# R450E.net
KiCad netlist of a schematic drawn in EAGLE
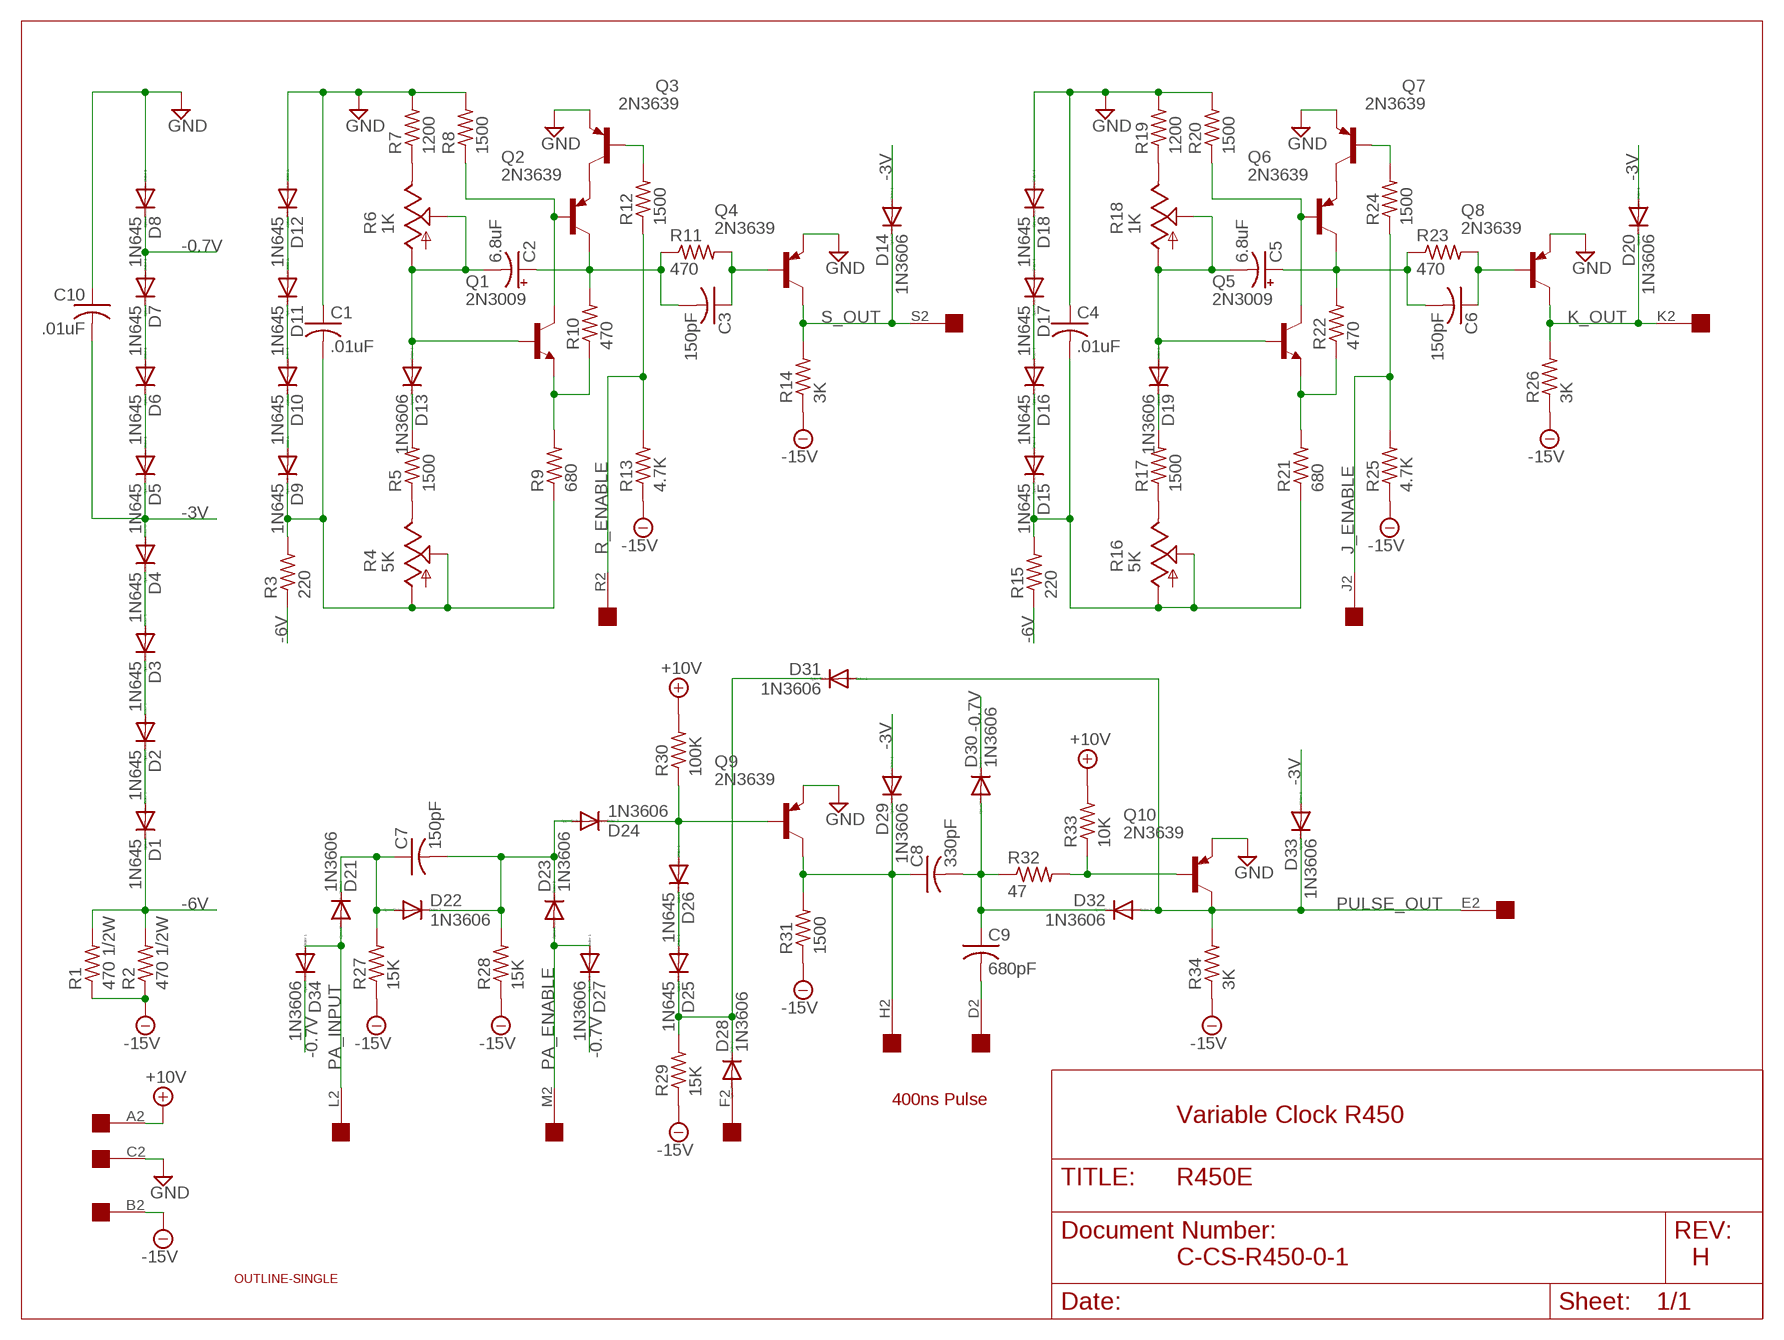
[diagram p0: schematic, sheet 1]

(export (version "E")
  (design (tool "Eeschema 10.0.6"))
  (components
    (comp (ref "C1")
      (value ".01uF")
      (footprint "eagle-import:C050-025X075")
      (libsource (lib "eagle-import") (part "C-US050-025X075"))
    )
    (comp (ref "C2")
      (value "6.8uF")
      (footprint "eagle-import:E12-4")
      (libsource (lib "eagle-import") (part "CPOL-USE12-4AXIAL"))
    )
    (comp (ref "C3")
      (value "150pF")
      (footprint "eagle-import:C075-032X103")
      (libsource (lib "eagle-import") (part "C-US075-032X103"))
    )
    (comp (ref "C4")
      (value ".01uF")
      (footprint "eagle-import:C050-025X075")
      (libsource (lib "eagle-import") (part "C-US050-025X075"))
    )
    (comp (ref "C5")
      (value "6.8uF")
      (footprint "eagle-import:E12-4")
      (libsource (lib "eagle-import") (part "CPOL-USE12-4AXIAL"))
    )
    (comp (ref "C6")
      (value "150pF")
      (footprint "eagle-import:C075-032X103")
      (libsource (lib "eagle-import") (part "C-US075-032X103"))
    )
    (comp (ref "C7")
      (value "150pF")
      (footprint "eagle-import:C075-032X103")
      (libsource (lib "eagle-import") (part "C-US075-032X103"))
    )
    (comp (ref "C8")
      (value "330pF")
      (footprint "eagle-import:C075-032X103")
      (libsource (lib "eagle-import") (part "C-US075-032X103"))
    )
    (comp (ref "C9")
      (value "680pF")
      (footprint "eagle-import:C075-032X103")
      (libsource (lib "eagle-import") (part "C-US075-032X103"))
    )
    (comp (ref "C10")
      (value ".01uF")
      (footprint "eagle-import:C050-025X075")
      (libsource (lib "eagle-import") (part "C-US050-025X075"))
    )
    (comp (ref "D1")
      (value "1N645")
      (footprint "eagle-import:DO35-10")
      (libsource (lib "eagle-import") (part "1N4148DO35-10"))
    )
    (comp (ref "D2")
      (value "1N645")
      (footprint "eagle-import:DO35-10")
      (libsource (lib "eagle-import") (part "1N4148DO35-10"))
    )
    (comp (ref "D3")
      (value "1N645")
      (footprint "eagle-import:DO35-10")
      (libsource (lib "eagle-import") (part "1N4148DO35-10"))
    )
    (comp (ref "D4")
      (value "1N645")
      (footprint "eagle-import:DO35-10")
      (libsource (lib "eagle-import") (part "1N4148DO35-10"))
    )
    (comp (ref "D5")
      (value "1N645")
      (footprint "eagle-import:DO35-10")
      (libsource (lib "eagle-import") (part "1N4148DO35-10"))
    )
    (comp (ref "D6")
      (value "1N645")
      (footprint "eagle-import:DO35-10")
      (libsource (lib "eagle-import") (part "1N4148DO35-10"))
    )
    (comp (ref "D7")
      (value "1N645")
      (footprint "eagle-import:DO35-10")
      (libsource (lib "eagle-import") (part "1N4148DO35-10"))
    )
    (comp (ref "D8")
      (value "1N645")
      (footprint "eagle-import:DO35-10")
      (libsource (lib "eagle-import") (part "1N4148DO35-10"))
    )
    (comp (ref "D9")
      (value "1N645")
      (footprint "eagle-import:DO35-10")
      (libsource (lib "eagle-import") (part "1N4148DO35-10"))
    )
    (comp (ref "D10")
      (value "1N645")
      (footprint "eagle-import:DO35-10")
      (libsource (lib "eagle-import") (part "1N4148DO35-10"))
    )
    (comp (ref "D11")
      (value "1N645")
      (footprint "eagle-import:DO35-10")
      (libsource (lib "eagle-import") (part "1N4148DO35-10"))
    )
    (comp (ref "D12")
      (value "1N645")
      (footprint "eagle-import:DO35-10")
      (libsource (lib "eagle-import") (part "1N4148DO35-10"))
    )
    (comp (ref "D13")
      (value "1N3606")
      (footprint "eagle-import:DO35-10")
      (libsource (lib "eagle-import") (part "1N4148DO35-10"))
    )
    (comp (ref "D14")
      (value "1N3606")
      (footprint "eagle-import:DO35-10")
      (libsource (lib "eagle-import") (part "1N4148DO35-10"))
    )
    (comp (ref "D15")
      (value "1N645")
      (footprint "eagle-import:DO35-10")
      (libsource (lib "eagle-import") (part "1N4148DO35-10"))
    )
    (comp (ref "D16")
      (value "1N645")
      (footprint "eagle-import:DO35-10")
      (libsource (lib "eagle-import") (part "1N4148DO35-10"))
    )
    (comp (ref "D17")
      (value "1N645")
      (footprint "eagle-import:DO35-10")
      (libsource (lib "eagle-import") (part "1N4148DO35-10"))
    )
    (comp (ref "D18")
      (value "1N645")
      (footprint "eagle-import:DO35-10")
      (libsource (lib "eagle-import") (part "1N4148DO35-10"))
    )
    (comp (ref "D19")
      (value "1N3606")
      (footprint "eagle-import:DO35-10")
      (libsource (lib "eagle-import") (part "1N4148DO35-10"))
    )
    (comp (ref "D20")
      (value "1N3606")
      (footprint "eagle-import:DO35-10")
      (libsource (lib "eagle-import") (part "1N4148DO35-10"))
    )
    (comp (ref "D21")
      (value "1N3606")
      (footprint "eagle-import:DO35-10")
      (libsource (lib "eagle-import") (part "1N4148DO35-10"))
    )
    (comp (ref "D22")
      (value "1N3606")
      (footprint "eagle-import:DO35-10")
      (libsource (lib "eagle-import") (part "1N4148DO35-10"))
    )
    (comp (ref "D23")
      (value "1N3606")
      (footprint "eagle-import:DO35-10")
      (libsource (lib "eagle-import") (part "1N4148DO35-10"))
    )
    (comp (ref "D24")
      (value "1N3606")
      (footprint "eagle-import:DO35-10")
      (libsource (lib "eagle-import") (part "1N4148DO35-10"))
    )
    (comp (ref "D25")
      (value "1N645")
      (footprint "eagle-import:DO35-10")
      (libsource (lib "eagle-import") (part "1N4148DO35-10"))
    )
    (comp (ref "D26")
      (value "1N645")
      (footprint "eagle-import:DO35-10")
      (libsource (lib "eagle-import") (part "1N4148DO35-10"))
    )
    (comp (ref "D27")
      (value "1N3606")
      (footprint "eagle-import:DO35-10")
      (libsource (lib "eagle-import") (part "1N4148DO35-10"))
    )
    (comp (ref "D28")
      (value "1N3606")
      (footprint "eagle-import:DO35-10")
      (libsource (lib "eagle-import") (part "1N4148DO35-10"))
    )
    (comp (ref "D29")
      (value "1N3606")
      (footprint "eagle-import:DO35-10")
      (libsource (lib "eagle-import") (part "1N4148DO35-10"))
    )
    (comp (ref "D30")
      (value "1N3606")
      (footprint "eagle-import:DO35-10")
      (libsource (lib "eagle-import") (part "1N4148DO35-10"))
    )
    (comp (ref "D31")
      (value "1N3606")
      (footprint "eagle-import:DO35-10")
      (libsource (lib "eagle-import") (part "1N4148DO35-10"))
    )
    (comp (ref "D32")
      (value "1N3606")
      (footprint "eagle-import:DO35-10")
      (libsource (lib "eagle-import") (part "1N4148DO35-10"))
    )
    (comp (ref "D33")
      (value "1N3606")
      (footprint "eagle-import:DO35-10")
      (libsource (lib "eagle-import") (part "1N4148DO35-10"))
    )
    (comp (ref "D34")
      (value "1N3606")
      (footprint "eagle-import:DO35-10")
      (libsource (lib "eagle-import") (part "1N4148DO35-10"))
    )
    (comp (ref "Q1")
      (value "2N3009")
      (footprint "eagle-import:TO5")
      (libsource (lib "eagle-import") (part "2N2102"))
    )
    (comp (ref "Q2")
      (value "2N3639")
      (footprint "eagle-import:TO39")
      (libsource (lib "eagle-import") (part "2N2904"))
    )
    (comp (ref "Q3")
      (value "2N3639")
      (footprint "eagle-import:TO39")
      (libsource (lib "eagle-import") (part "2N2904"))
    )
    (comp (ref "Q4")
      (value "2N3639")
      (footprint "eagle-import:TO39")
      (libsource (lib "eagle-import") (part "2N2904"))
    )
    (comp (ref "Q5")
      (value "2N3009")
      (footprint "eagle-import:TO5")
      (libsource (lib "eagle-import") (part "2N2102"))
    )
    (comp (ref "Q6")
      (value "2N3639")
      (footprint "eagle-import:TO39")
      (libsource (lib "eagle-import") (part "2N2904"))
    )
    (comp (ref "Q7")
      (value "2N3639")
      (footprint "eagle-import:TO39")
      (libsource (lib "eagle-import") (part "2N2904"))
    )
    (comp (ref "Q8")
      (value "2N3639")
      (footprint "eagle-import:TO39")
      (libsource (lib "eagle-import") (part "2N2904"))
    )
    (comp (ref "Q9")
      (value "2N3639")
      (footprint "eagle-import:TO39")
      (libsource (lib "eagle-import") (part "2N2904"))
    )
    (comp (ref "Q10")
      (value "2N3639")
      (footprint "eagle-import:TO39")
      (libsource (lib "eagle-import") (part "2N2904"))
    )
    (comp (ref "R1")
      (value "470 1/2W")
      (footprint "eagle-import:0411_15")
      (libsource (lib "eagle-import") (part "R-US_0411/15"))
    )
    (comp (ref "R2")
      (value "470 1/2W")
      (footprint "eagle-import:0411_15")
      (libsource (lib "eagle-import") (part "R-US_0411/15"))
    )
    (comp (ref "R3")
      (value "220")
      (footprint "eagle-import:0207_10")
      (libsource (lib "eagle-import") (part "R-US_0207/10"))
    )
    (comp (ref "R4")
      (value "5K")
      (footprint "eagle-import:CT6")
      (libsource (lib "eagle-import") (part "TRIM_US-CT6"))
    )
    (comp (ref "R5")
      (value "1500")
      (footprint "eagle-import:0207_10")
      (libsource (lib "eagle-import") (part "R-US_0207/10"))
    )
    (comp (ref "R6")
      (value "1K")
      (footprint "eagle-import:CT6")
      (libsource (lib "eagle-import") (part "TRIM_US-CT6"))
    )
    (comp (ref "R7")
      (value "1200")
      (footprint "eagle-import:0207_10")
      (libsource (lib "eagle-import") (part "R-US_0207/10"))
    )
    (comp (ref "R8")
      (value "1500")
      (footprint "eagle-import:0207_10")
      (libsource (lib "eagle-import") (part "R-US_0207/10"))
    )
    (comp (ref "R9")
      (value "680")
      (footprint "eagle-import:0207_10")
      (libsource (lib "eagle-import") (part "R-US_0207/10"))
    )
    (comp (ref "R10")
      (value "470")
      (footprint "eagle-import:0207_10")
      (libsource (lib "eagle-import") (part "R-US_0207/10"))
    )
    (comp (ref "R11")
      (value "470")
      (footprint "eagle-import:0207_10")
      (libsource (lib "eagle-import") (part "R-US_0207/10"))
    )
    (comp (ref "R12")
      (value "1500")
      (footprint "eagle-import:0207_10")
      (libsource (lib "eagle-import") (part "R-US_0207/10"))
    )
    (comp (ref "R13")
      (value "4.7K")
      (footprint "eagle-import:0207_10")
      (libsource (lib "eagle-import") (part "R-US_0207/10"))
    )
    (comp (ref "R14")
      (value "3K")
      (footprint "eagle-import:0207_10")
      (libsource (lib "eagle-import") (part "R-US_0207/10"))
    )
    (comp (ref "R15")
      (value "220")
      (footprint "eagle-import:0207_10")
      (libsource (lib "eagle-import") (part "R-US_0207/10"))
    )
    (comp (ref "R16")
      (value "5K")
      (footprint "eagle-import:CT6")
      (libsource (lib "eagle-import") (part "TRIM_US-CT6"))
    )
    (comp (ref "R17")
      (value "1500")
      (footprint "eagle-import:0207_10")
      (libsource (lib "eagle-import") (part "R-US_0207/10"))
    )
    (comp (ref "R18")
      (value "1K")
      (footprint "eagle-import:CT6")
      (libsource (lib "eagle-import") (part "TRIM_US-CT6"))
    )
    (comp (ref "R19")
      (value "1200")
      (footprint "eagle-import:0207_10")
      (libsource (lib "eagle-import") (part "R-US_0207/10"))
    )
    (comp (ref "R20")
      (value "1500")
      (footprint "eagle-import:0207_10")
      (libsource (lib "eagle-import") (part "R-US_0207/10"))
    )
    (comp (ref "R21")
      (value "680")
      (footprint "eagle-import:0207_10")
      (libsource (lib "eagle-import") (part "R-US_0207/10"))
    )
    (comp (ref "R22")
      (value "470")
      (footprint "eagle-import:0207_10")
      (libsource (lib "eagle-import") (part "R-US_0207/10"))
    )
    (comp (ref "R23")
      (value "470")
      (footprint "eagle-import:0207_10")
      (libsource (lib "eagle-import") (part "R-US_0207/10"))
    )
    (comp (ref "R24")
      (value "1500")
      (footprint "eagle-import:0207_10")
      (libsource (lib "eagle-import") (part "R-US_0207/10"))
    )
    (comp (ref "R25")
      (value "4.7K")
      (footprint "eagle-import:0207_10")
      (libsource (lib "eagle-import") (part "R-US_0207/10"))
    )
    (comp (ref "R26")
      (value "3K")
      (footprint "eagle-import:0207_10")
      (libsource (lib "eagle-import") (part "R-US_0207/10"))
    )
    (comp (ref "R27")
      (value "15K")
      (footprint "eagle-import:0207_10")
      (libsource (lib "eagle-import") (part "R-US_0207/10"))
    )
    (comp (ref "R28")
      (value "15K")
      (footprint "eagle-import:0207_10")
      (libsource (lib "eagle-import") (part "R-US_0207/10"))
    )
    (comp (ref "R29")
      (value "15K")
      (footprint "eagle-import:0207_10")
      (libsource (lib "eagle-import") (part "R-US_0207/10"))
    )
    (comp (ref "R30")
      (value "100K")
      (footprint "eagle-import:0207_10")
      (libsource (lib "eagle-import") (part "R-US_0207/10"))
    )
    (comp (ref "R31")
      (value "1500")
      (footprint "eagle-import:0207_10")
      (libsource (lib "eagle-import") (part "R-US_0207/10"))
    )
    (comp (ref "R32")
      (value "47")
      (footprint "eagle-import:0207_10")
      (libsource (lib "eagle-import") (part "R-US_0207/10"))
    )
    (comp (ref "R33")
      (value "10K")
      (footprint "eagle-import:0207_10")
      (libsource (lib "eagle-import") (part "R-US_0207/10"))
    )
    (comp (ref "R34")
      (value "3K")
      (footprint "eagle-import:0207_10")
      (libsource (lib "eagle-import") (part "R-US_0207/10"))
    )
    (comp (ref "U$1")
      (value "OUTLINE-SINGLE")
      (footprint "eagle-import:SINGLE")
      (libsource (lib "eagle-import") (part "OUTLINE-SINGLE"))
    )
    (comp (ref "U$2")
      (value "EDGE-1")
      (footprint "eagle-import:EDGE-CON1")
      (libsource (lib "eagle-import") (part "EDGE-1"))
    )
  )
  (nets
    (net (code "1") (name "+10V") (class "Default")
      (node (ref "R30") (pin "2") (pinfunction "2_2") (pintype "passive"))
      (node (ref "R33") (pin "2") (pinfunction "2_2") (pintype "passive"))
      (node (ref "U$2") (pin "A2") (pinfunction "1_A2") (pintype "bidirectional"))
    )
    (net (code "2") (name "-15V") (class "Default")
      (node (ref "R1") (pin "1") (pinfunction "1_1") (pintype "passive"))
      (node (ref "R13") (pin "1") (pinfunction "1_1") (pintype "passive"))
      (node (ref "R14") (pin "1") (pinfunction "1_1") (pintype "passive"))
      (node (ref "R2") (pin "1") (pinfunction "1_1") (pintype "passive"))
      (node (ref "R25") (pin "1") (pinfunction "1_1") (pintype "passive"))
      (node (ref "R26") (pin "1") (pinfunction "1_1") (pintype "passive"))
      (node (ref "R27") (pin "1") (pinfunction "1_1") (pintype "passive"))
      (node (ref "R28") (pin "1") (pinfunction "1_1") (pintype "passive"))
      (node (ref "R29") (pin "1") (pinfunction "1_1") (pintype "passive"))
      (node (ref "R31") (pin "1") (pinfunction "1_1") (pintype "passive"))
      (node (ref "R34") (pin "1") (pinfunction "1_1") (pintype "passive"))
      (node (ref "U$2") (pin "B2") (pinfunction "1_B2") (pintype "bidirectional"))
    )
    (net (code "3") (name "/-0.7V") (class "Default")
      (node (ref "D27") (pin "C") (pinfunction "C_C") (pintype "passive"))
      (node (ref "D30") (pin "C") (pinfunction "C_C") (pintype "passive"))
      (node (ref "D34") (pin "C") (pinfunction "C_C") (pintype "passive"))
      (node (ref "D7") (pin "A") (pinfunction "A_A") (pintype "passive"))
      (node (ref "D8") (pin "C") (pinfunction "C_C") (pintype "passive"))
    )
    (net (code "4") (name "/-3V") (class "Default")
      (node (ref "C10") (pin "2") (pinfunction "2_2") (pintype "passive"))
      (node (ref "D14") (pin "A") (pinfunction "A_A") (pintype "passive"))
      (node (ref "D20") (pin "A") (pinfunction "A_A") (pintype "passive"))
      (node (ref "D29") (pin "A") (pinfunction "A_A") (pintype "passive"))
      (node (ref "D33") (pin "A") (pinfunction "A_A") (pintype "passive"))
      (node (ref "D4") (pin "A") (pinfunction "A_A") (pintype "passive"))
      (node (ref "D5") (pin "C") (pinfunction "C_C") (pintype "passive"))
    )
    (net (code "5") (name "/-6V") (class "Default")
      (node (ref "D1") (pin "C") (pinfunction "C_C") (pintype "passive"))
      (node (ref "R1") (pin "2") (pinfunction "2_2") (pintype "passive"))
      (node (ref "R15") (pin "1") (pinfunction "1_1") (pintype "passive"))
      (node (ref "R2") (pin "2") (pinfunction "2_2") (pintype "passive"))
      (node (ref "R3") (pin "1") (pinfunction "1_1") (pintype "passive"))
    )
    (net (code "6") (name "/J_ENABLE") (class "Default")
      (node (ref "R24") (pin "1") (pinfunction "1_1") (pintype "passive"))
      (node (ref "R25") (pin "2") (pinfunction "2_2") (pintype "passive"))
      (node (ref "U$2") (pin "J2") (pinfunction "1_J2") (pintype "bidirectional"))
    )
    (net (code "7") (name "/K_OUT") (class "Default")
      (node (ref "D20") (pin "C") (pinfunction "C_C") (pintype "passive"))
      (node (ref "Q8") (pin "3") (pinfunction "C_3") (pintype "passive"))
      (node (ref "R26") (pin "2") (pinfunction "2_2") (pintype "passive"))
      (node (ref "U$2") (pin "K2") (pinfunction "1_K2") (pintype "bidirectional"))
    )
    (net (code "8") (name "/PA_ENABLE") (class "Default")
      (node (ref "D23") (pin "A") (pinfunction "A_A") (pintype "passive"))
      (node (ref "D27") (pin "A") (pinfunction "A_A") (pintype "passive"))
      (node (ref "U$2") (pin "M2") (pinfunction "1_M2") (pintype "bidirectional"))
    )
    (net (code "9") (name "/PA_INPUT") (class "Default")
      (node (ref "D21") (pin "A") (pinfunction "A_A") (pintype "passive"))
      (node (ref "D34") (pin "A") (pinfunction "A_A") (pintype "passive"))
      (node (ref "U$2") (pin "L2") (pinfunction "1_L2") (pintype "bidirectional"))
    )
    (net (code "10") (name "/PULSE_OUT") (class "Default")
      (node (ref "D31") (pin "A") (pinfunction "A_A") (pintype "passive"))
      (node (ref "D32") (pin "A") (pinfunction "A_A") (pintype "passive"))
      (node (ref "D33") (pin "C") (pinfunction "C_C") (pintype "passive"))
      (node (ref "Q10") (pin "3") (pinfunction "C_3") (pintype "passive"))
      (node (ref "R34") (pin "2") (pinfunction "2_2") (pintype "passive"))
      (node (ref "U$2") (pin "E2") (pinfunction "1_E2") (pintype "bidirectional"))
    )
    (net (code "11") (name "/R_ENABLE") (class "Default")
      (node (ref "R12") (pin "1") (pinfunction "1_1") (pintype "passive"))
      (node (ref "R13") (pin "2") (pinfunction "2_2") (pintype "passive"))
      (node (ref "U$2") (pin "R2") (pinfunction "1_R2") (pintype "bidirectional"))
    )
    (net (code "12") (name "/S_OUT") (class "Default")
      (node (ref "D14") (pin "C") (pinfunction "C_C") (pintype "passive"))
      (node (ref "Q4") (pin "3") (pinfunction "C_3") (pintype "passive"))
      (node (ref "R14") (pin "2") (pinfunction "2_2") (pintype "passive"))
      (node (ref "U$2") (pin "S2") (pinfunction "1_S2") (pintype "bidirectional"))
    )
    (net (code "13") (name "GND") (class "Default")
      (node (ref "C1") (pin "1") (pinfunction "1_1") (pintype "passive"))
      (node (ref "C10") (pin "1") (pinfunction "1_1") (pintype "passive"))
      (node (ref "C4") (pin "1") (pinfunction "1_1") (pintype "passive"))
      (node (ref "D12") (pin "A") (pinfunction "A_A") (pintype "passive"))
      (node (ref "D18") (pin "A") (pinfunction "A_A") (pintype "passive"))
      (node (ref "D8") (pin "A") (pinfunction "A_A") (pintype "passive"))
      (node (ref "Q10") (pin "1") (pinfunction "E_1") (pintype "passive"))
      (node (ref "Q3") (pin "1") (pinfunction "E_1") (pintype "passive"))
      (node (ref "Q4") (pin "1") (pinfunction "E_1") (pintype "passive"))
      (node (ref "Q7") (pin "1") (pinfunction "E_1") (pintype "passive"))
      (node (ref "Q8") (pin "1") (pinfunction "E_1") (pintype "passive"))
      (node (ref "Q9") (pin "1") (pinfunction "E_1") (pintype "passive"))
      (node (ref "R19") (pin "2") (pinfunction "2_2") (pintype "passive"))
      (node (ref "R20") (pin "2") (pinfunction "2_2") (pintype "passive"))
      (node (ref "R7") (pin "2") (pinfunction "2_2") (pintype "passive"))
      (node (ref "R8") (pin "2") (pinfunction "2_2") (pintype "passive"))
      (node (ref "U$2") (pin "C2") (pinfunction "1_C2") (pintype "bidirectional"))
    )
    (net (code "14") (name "Net-(C1-Pad2)") (class "Default")
      (node (ref "C1") (pin "2") (pinfunction "2_2") (pintype "passive"))
      (node (ref "D9") (pin "C") (pinfunction "C_C") (pintype "passive"))
      (node (ref "R3") (pin "2") (pinfunction "2_2") (pintype "passive"))
      (node (ref "R4") (pin "A") (pinfunction "A_A") (pintype "passive"))
      (node (ref "R4") (pin "S") (pinfunction "S_S") (pintype "passive"))
      (node (ref "R9") (pin "1") (pinfunction "1_1") (pintype "passive"))
    )
    (net (code "15") (name "Net-(C4-Pad2)") (class "Default")
      (node (ref "C4") (pin "2") (pinfunction "2_2") (pintype "passive"))
      (node (ref "D15") (pin "C") (pinfunction "C_C") (pintype "passive"))
      (node (ref "R15") (pin "2") (pinfunction "2_2") (pintype "passive"))
      (node (ref "R16") (pin "A") (pinfunction "A_A") (pintype "passive"))
      (node (ref "R16") (pin "S") (pinfunction "S_S") (pintype "passive"))
      (node (ref "R21") (pin "1") (pinfunction "1_1") (pintype "passive"))
    )
    (net (code "16") (name "Net-(C7-Pad1)") (class "Default")
      (node (ref "C7") (pin "1") (pinfunction "1_1") (pintype "passive"))
      (node (ref "D21") (pin "C") (pinfunction "C_C") (pintype "passive"))
      (node (ref "D22") (pin "A") (pinfunction "A_A") (pintype "passive"))
      (node (ref "R27") (pin "2") (pinfunction "2_2") (pintype "passive"))
    )
    (net (code "17") (name "Net-(C7-Pad2)") (class "Default")
      (node (ref "C7") (pin "2") (pinfunction "2_2") (pintype "passive"))
      (node (ref "D22") (pin "C") (pinfunction "C_C") (pintype "passive"))
      (node (ref "D23") (pin "C") (pinfunction "C_C") (pintype "passive"))
      (node (ref "D24") (pin "A") (pinfunction "A_A") (pintype "passive"))
      (node (ref "R28") (pin "2") (pinfunction "2_2") (pintype "passive"))
    )
    (net (code "18") (name "Net-(C8-Pad2)") (class "Default")
      (node (ref "C8") (pin "2") (pinfunction "2_2") (pintype "passive"))
      (node (ref "C9") (pin "1") (pinfunction "1_1") (pintype "passive"))
      (node (ref "D30") (pin "A") (pinfunction "A_A") (pintype "passive"))
      (node (ref "D32") (pin "C") (pinfunction "C_C") (pintype "passive"))
      (node (ref "R32") (pin "1") (pinfunction "1_1") (pintype "passive"))
    )
    (net (code "19") (name "Net-(D1-PadA)") (class "Default")
      (node (ref "D1") (pin "A") (pinfunction "A_A") (pintype "passive"))
      (node (ref "D2") (pin "C") (pinfunction "C_C") (pintype "passive"))
    )
    (net (code "20") (name "Net-(D2-PadA)") (class "Default")
      (node (ref "D2") (pin "A") (pinfunction "A_A") (pintype "passive"))
      (node (ref "D3") (pin "C") (pinfunction "C_C") (pintype "passive"))
    )
    (net (code "21") (name "Net-(D3-PadA)") (class "Default")
      (node (ref "D3") (pin "A") (pinfunction "A_A") (pintype "passive"))
      (node (ref "D4") (pin "C") (pinfunction "C_C") (pintype "passive"))
    )
    (net (code "22") (name "Net-(D5-PadA)") (class "Default")
      (node (ref "D5") (pin "A") (pinfunction "A_A") (pintype "passive"))
      (node (ref "D6") (pin "C") (pinfunction "C_C") (pintype "passive"))
    )
    (net (code "23") (name "Net-(D6-PadA)") (class "Default")
      (node (ref "D6") (pin "A") (pinfunction "A_A") (pintype "passive"))
      (node (ref "D7") (pin "C") (pinfunction "C_C") (pintype "passive"))
    )
    (net (code "24") (name "Net-(D10-PadA)") (class "Default")
      (node (ref "D10") (pin "A") (pinfunction "A_A") (pintype "passive"))
      (node (ref "D11") (pin "C") (pinfunction "C_C") (pintype "passive"))
    )
    (net (code "25") (name "Net-(D10-PadC)") (class "Default")
      (node (ref "D10") (pin "C") (pinfunction "C_C") (pintype "passive"))
      (node (ref "D9") (pin "A") (pinfunction "A_A") (pintype "passive"))
    )
    (net (code "26") (name "Net-(D11-PadA)") (class "Default")
      (node (ref "D11") (pin "A") (pinfunction "A_A") (pintype "passive"))
      (node (ref "D12") (pin "C") (pinfunction "C_C") (pintype "passive"))
    )
    (net (code "27") (name "Net-(D13-PadC)") (class "Default")
      (node (ref "D13") (pin "C") (pinfunction "C_C") (pintype "passive"))
      (node (ref "R5") (pin "2") (pinfunction "2_2") (pintype "passive"))
    )
    (net (code "28") (name "Net-(D15-PadA)") (class "Default")
      (node (ref "D15") (pin "A") (pinfunction "A_A") (pintype "passive"))
      (node (ref "D16") (pin "C") (pinfunction "C_C") (pintype "passive"))
    )
    (net (code "29") (name "Net-(D16-PadA)") (class "Default")
      (node (ref "D16") (pin "A") (pinfunction "A_A") (pintype "passive"))
      (node (ref "D17") (pin "C") (pinfunction "C_C") (pintype "passive"))
    )
    (net (code "30") (name "Net-(D17-PadA)") (class "Default")
      (node (ref "D17") (pin "A") (pinfunction "A_A") (pintype "passive"))
      (node (ref "D18") (pin "C") (pinfunction "C_C") (pintype "passive"))
    )
    (net (code "31") (name "Net-(D19-PadC)") (class "Default")
      (node (ref "D19") (pin "C") (pinfunction "C_C") (pintype "passive"))
      (node (ref "R17") (pin "2") (pinfunction "2_2") (pintype "passive"))
    )
    (net (code "32") (name "Net-(D25-PadA)") (class "Default")
      (node (ref "D25") (pin "A") (pinfunction "A_A") (pintype "passive"))
      (node (ref "D26") (pin "C") (pinfunction "C_C") (pintype "passive"))
    )
    (net (code "33") (name "Net-(D25-PadC)") (class "Default")
      (node (ref "D25") (pin "C") (pinfunction "C_C") (pintype "passive"))
      (node (ref "D28") (pin "C") (pinfunction "C_C") (pintype "passive"))
      (node (ref "D31") (pin "C") (pinfunction "C_C") (pintype "passive"))
      (node (ref "R29") (pin "2") (pinfunction "2_2") (pintype "passive"))
    )
    (net (code "34") (name "Net-(Q1-B)") (class "Default")
      (node (ref "C2") (pin "-") (pinfunction "-_-") (pintype "passive"))
      (node (ref "D13") (pin "A") (pinfunction "A_A") (pintype "passive"))
      (node (ref "Q1") (pin "2") (pinfunction "B_2") (pintype "passive"))
      (node (ref "R6") (pin "A") (pinfunction "A_A") (pintype "passive"))
      (node (ref "R6") (pin "S") (pinfunction "S_S") (pintype "passive"))
    )
    (net (code "35") (name "Net-(Q1-C)") (class "Default")
      (node (ref "Q1") (pin "3") (pinfunction "C_3") (pintype "passive"))
      (node (ref "Q2") (pin "2") (pinfunction "B_2") (pintype "passive"))
      (node (ref "R8") (pin "1") (pinfunction "1_1") (pintype "passive"))
    )
    (net (code "36") (name "Net-(Q1-E)") (class "Default")
      (node (ref "Q1") (pin "1") (pinfunction "E_1") (pintype "passive"))
      (node (ref "R10") (pin "1") (pinfunction "1_1") (pintype "passive"))
      (node (ref "R9") (pin "2") (pinfunction "2_2") (pintype "passive"))
    )
    (net (code "37") (name "Net-(Q2-C)") (class "Default")
      (node (ref "C2") (pin "+") (pinfunction "+_+") (pintype "passive"))
      (node (ref "C3") (pin "2") (pinfunction "2_2") (pintype "passive"))
      (node (ref "Q2") (pin "3") (pinfunction "C_3") (pintype "passive"))
      (node (ref "R10") (pin "2") (pinfunction "2_2") (pintype "passive"))
      (node (ref "R11") (pin "1") (pinfunction "1_1") (pintype "passive"))
    )
    (net (code "38") (name "Net-(Q2-E)") (class "Default")
      (node (ref "Q2") (pin "1") (pinfunction "E_1") (pintype "passive"))
      (node (ref "Q3") (pin "3") (pinfunction "C_3") (pintype "passive"))
    )
    (net (code "39") (name "Net-(Q3-B)") (class "Default")
      (node (ref "Q3") (pin "2") (pinfunction "B_2") (pintype "passive"))
      (node (ref "R12") (pin "2") (pinfunction "2_2") (pintype "passive"))
    )
    (net (code "40") (name "Net-(Q4-B)") (class "Default")
      (node (ref "C3") (pin "1") (pinfunction "1_1") (pintype "passive"))
      (node (ref "Q4") (pin "2") (pinfunction "B_2") (pintype "passive"))
      (node (ref "R11") (pin "2") (pinfunction "2_2") (pintype "passive"))
    )
    (net (code "41") (name "Net-(Q5-B)") (class "Default")
      (node (ref "C5") (pin "-") (pinfunction "-_-") (pintype "passive"))
      (node (ref "D19") (pin "A") (pinfunction "A_A") (pintype "passive"))
      (node (ref "Q5") (pin "2") (pinfunction "B_2") (pintype "passive"))
      (node (ref "R18") (pin "A") (pinfunction "A_A") (pintype "passive"))
      (node (ref "R18") (pin "S") (pinfunction "S_S") (pintype "passive"))
    )
    (net (code "42") (name "Net-(Q5-C)") (class "Default")
      (node (ref "Q5") (pin "3") (pinfunction "C_3") (pintype "passive"))
      (node (ref "Q6") (pin "2") (pinfunction "B_2") (pintype "passive"))
      (node (ref "R20") (pin "1") (pinfunction "1_1") (pintype "passive"))
    )
    (net (code "43") (name "Net-(Q5-E)") (class "Default")
      (node (ref "Q5") (pin "1") (pinfunction "E_1") (pintype "passive"))
      (node (ref "R21") (pin "2") (pinfunction "2_2") (pintype "passive"))
      (node (ref "R22") (pin "1") (pinfunction "1_1") (pintype "passive"))
    )
    (net (code "44") (name "Net-(Q6-C)") (class "Default")
      (node (ref "C5") (pin "+") (pinfunction "+_+") (pintype "passive"))
      (node (ref "C6") (pin "2") (pinfunction "2_2") (pintype "passive"))
      (node (ref "Q6") (pin "3") (pinfunction "C_3") (pintype "passive"))
      (node (ref "R22") (pin "2") (pinfunction "2_2") (pintype "passive"))
      (node (ref "R23") (pin "1") (pinfunction "1_1") (pintype "passive"))
    )
    (net (code "45") (name "Net-(Q6-E)") (class "Default")
      (node (ref "Q6") (pin "1") (pinfunction "E_1") (pintype "passive"))
      (node (ref "Q7") (pin "3") (pinfunction "C_3") (pintype "passive"))
    )
    (net (code "46") (name "Net-(Q7-B)") (class "Default")
      (node (ref "Q7") (pin "2") (pinfunction "B_2") (pintype "passive"))
      (node (ref "R24") (pin "2") (pinfunction "2_2") (pintype "passive"))
    )
    (net (code "47") (name "Net-(Q8-B)") (class "Default")
      (node (ref "C6") (pin "1") (pinfunction "1_1") (pintype "passive"))
      (node (ref "Q8") (pin "2") (pinfunction "B_2") (pintype "passive"))
      (node (ref "R23") (pin "2") (pinfunction "2_2") (pintype "passive"))
    )
    (net (code "48") (name "Net-(Q9-B)") (class "Default")
      (node (ref "D24") (pin "C") (pinfunction "C_C") (pintype "passive"))
      (node (ref "D26") (pin "A") (pinfunction "A_A") (pintype "passive"))
      (node (ref "Q9") (pin "2") (pinfunction "B_2") (pintype "passive"))
      (node (ref "R30") (pin "1") (pinfunction "1_1") (pintype "passive"))
    )
    (net (code "49") (name "Net-(Q9-C)") (class "Default")
      (node (ref "C8") (pin "1") (pinfunction "1_1") (pintype "passive"))
      (node (ref "D29") (pin "C") (pinfunction "C_C") (pintype "passive"))
      (node (ref "Q9") (pin "3") (pinfunction "C_3") (pintype "passive"))
      (node (ref "R31") (pin "2") (pinfunction "2_2") (pintype "passive"))
      (node (ref "U$2") (pin "H2") (pinfunction "1_H2") (pintype "bidirectional"))
    )
    (net (code "50") (name "Net-(Q10-B)") (class "Default")
      (node (ref "Q10") (pin "2") (pinfunction "B_2") (pintype "passive"))
      (node (ref "R32") (pin "2") (pinfunction "2_2") (pintype "passive"))
      (node (ref "R33") (pin "1") (pinfunction "1_1") (pintype "passive"))
    )
    (net (code "51") (name "Net-(R4-PadE)") (class "Default")
      (node (ref "R4") (pin "E") (pinfunction "E_E") (pintype "passive"))
      (node (ref "R5") (pin "1") (pinfunction "1_1") (pintype "passive"))
    )
    (net (code "52") (name "Net-(R6-PadE)") (class "Default")
      (node (ref "R6") (pin "E") (pinfunction "E_E") (pintype "passive"))
      (node (ref "R7") (pin "1") (pinfunction "1_1") (pintype "passive"))
    )
    (net (code "53") (name "Net-(R16-PadE)") (class "Default")
      (node (ref "R16") (pin "E") (pinfunction "E_E") (pintype "passive"))
      (node (ref "R17") (pin "1") (pinfunction "1_1") (pintype "passive"))
    )
    (net (code "54") (name "Net-(R18-PadE)") (class "Default")
      (node (ref "R18") (pin "E") (pinfunction "E_E") (pintype "passive"))
      (node (ref "R19") (pin "1") (pinfunction "1_1") (pintype "passive"))
    )
    (net (code "55") (name "Net-(U$2D-1)") (class "Default")
      (node (ref "C9") (pin "2") (pinfunction "2_2") (pintype "passive"))
      (node (ref "U$2") (pin "D2") (pinfunction "1_D2") (pintype "bidirectional"))
    )
    (net (code "56") (name "Net-(U$2F-1)") (class "Default")
      (node (ref "D28") (pin "A") (pinfunction "A_A") (pintype "passive"))
      (node (ref "U$2") (pin "F2") (pinfunction "1_F2") (pintype "bidirectional"))
    )
  )
)
